# Trace_antenna_final_RFID_v10.net
KiCad netlist of a schematic drawn in EAGLE
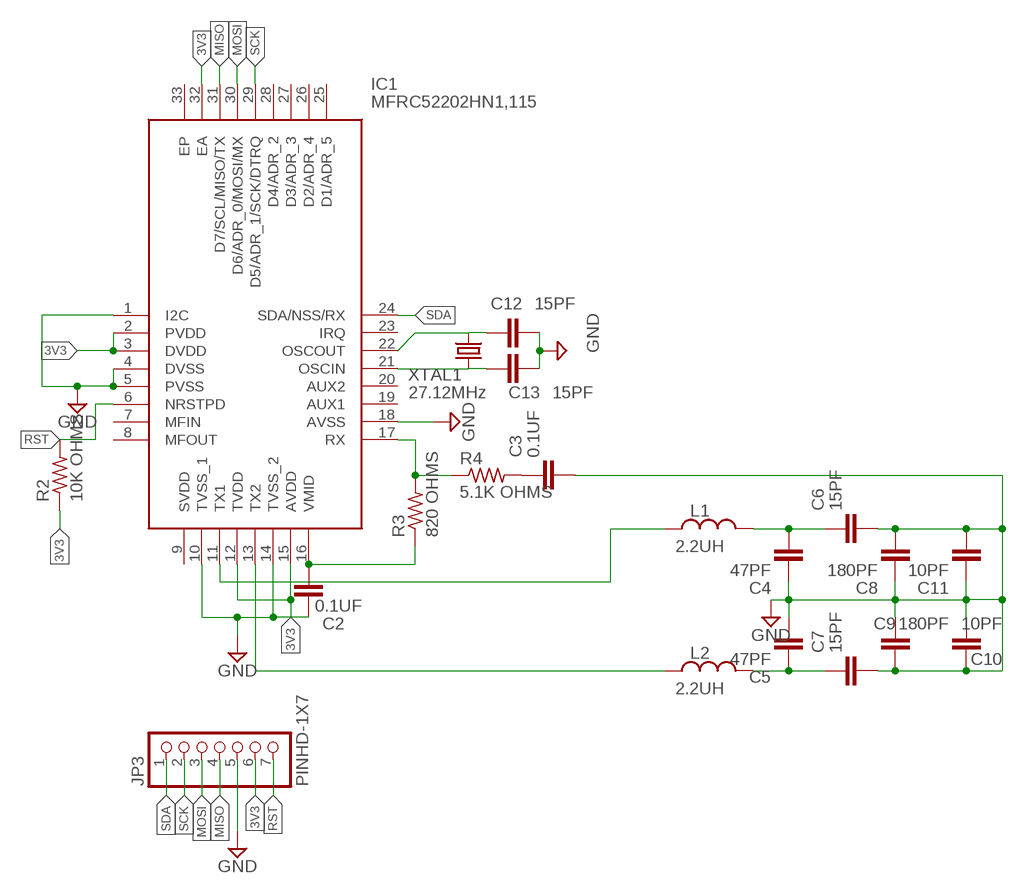
[diagram p0: schematic, sheet 1]

(export (version "E")
  (design (tool "Eeschema 10.0.6"))
  (components
    (comp (ref "C2")
      (value "0.1UF")
      (footprint "eagle-import:CAPC2012X110")
      (libsource (lib "eagle-import") (part "CCHIP-0805(2012-METRIC)_"))
    )
    (comp (ref "C3")
      (value "0.1UF")
      (footprint "eagle-import:CAPC2012X110")
      (libsource (lib "eagle-import") (part "CCHIP-0805(2012-METRIC)_"))
    )
    (comp (ref "C4")
      (value "47PF")
      (footprint "eagle-import:CAPC2012X110")
      (libsource (lib "eagle-import") (part "CCHIP-0805(2012-METRIC)_"))
    )
    (comp (ref "C5")
      (value "47PF")
      (footprint "eagle-import:CAPC2012X110")
      (libsource (lib "eagle-import") (part "CCHIP-0805(2012-METRIC)_"))
    )
    (comp (ref "C6")
      (value "15PF")
      (footprint "eagle-import:CAPC2012X110")
      (libsource (lib "eagle-import") (part "CCHIP-0805(2012-METRIC)_"))
    )
    (comp (ref "C7")
      (value "15PF")
      (footprint "eagle-import:CAPC2012X110")
      (libsource (lib "eagle-import") (part "CCHIP-0805(2012-METRIC)_"))
    )
    (comp (ref "C8")
      (value "180PF")
      (footprint "eagle-import:CAPC2012X110")
      (libsource (lib "eagle-import") (part "CCHIP-0805(2012-METRIC)_"))
    )
    (comp (ref "C9")
      (value "180PF")
      (footprint "eagle-import:CAPC2012X110")
      (libsource (lib "eagle-import") (part "CCHIP-0805(2012-METRIC)_"))
    )
    (comp (ref "C10")
      (value "10PF")
      (footprint "eagle-import:CAPC2012X110")
      (libsource (lib "eagle-import") (part "CCHIP-0805(2012-METRIC)_"))
    )
    (comp (ref "C11")
      (value "10PF")
      (footprint "eagle-import:CAPC2012X110")
      (libsource (lib "eagle-import") (part "CCHIP-0805(2012-METRIC)_"))
    )
    (comp (ref "C12")
      (value "15PF")
      (footprint "eagle-import:CAPC2012X110")
      (libsource (lib "eagle-import") (part "CCHIP-0805(2012-METRIC)_"))
    )
    (comp (ref "C13")
      (value "15PF")
      (footprint "eagle-import:CAPC2012X110")
      (libsource (lib "eagle-import") (part "CCHIP-0805(2012-METRIC)_"))
    )
    (comp (ref "IC1")
      (value "MFRC52202HN1,115")
      (footprint "eagle-import:QFN50P500X500X100-33N")
      (fields (field (name "MOUSER_PART_NUMBER") "771-MFRC52202HN1115"))
      (libsource (lib "eagle-import") (part "MFRC52202HN1,115"))
    )
    (comp (ref "JP3")
      (value "PINHD-1X7")
      (footprint "eagle-import:1X07")
      (libsource (lib "eagle-import") (part "PINHD-1X7"))
    )
    (comp (ref "L1")
      (value "2.2UH")
      (footprint "eagle-import:INDC2009X120")
      (libsource (lib "eagle-import") (part "LCHIP-0805(2012-METRIC)_"))
    )
    (comp (ref "L2")
      (value "2.2UH")
      (footprint "eagle-import:INDC2009X120")
      (libsource (lib "eagle-import") (part "LCHIP-0805(2012-METRIC)_"))
    )
    (comp (ref "R2")
      (value "10K OHMS")
      (footprint "eagle-import:RESC2012X65")
      (libsource (lib "eagle-import") (part "R-USCHIP-0805(2012-METRIC)_"))
    )
    (comp (ref "R3")
      (value "820 OHMS")
      (footprint "eagle-import:RESC2012X65")
      (libsource (lib "eagle-import") (part "R-USCHIP-0805(2012-METRIC)_"))
    )
    (comp (ref "R4")
      (value "5.1K OHMS")
      (footprint "eagle-import:RESC2012X65")
      (libsource (lib "eagle-import") (part "R-USCHIP-0805(2012-METRIC)_"))
    )
    (comp (ref "XTAL1")
      (value "27.12MHz")
      (footprint "eagle-import:XTALRR488W45L1150T500H350B")
      (libsource (lib "eagle-import") (part "CRYSTALHC49-11.5L_"))
    )
  )
  (nets
    (net (code "1") (name "3V3") (class "Default")
      (node (ref "IC1") (pin "12") (pinfunction "TVDD_12") (pintype "bidirectional"))
      (node (ref "IC1") (pin "15") (pinfunction "AVDD_15") (pintype "bidirectional"))
      (node (ref "IC1") (pin "2") (pinfunction "PVDD_2") (pintype "bidirectional"))
      (node (ref "IC1") (pin "3") (pinfunction "DVDD_3") (pintype "bidirectional"))
      (node (ref "IC1") (pin "32") (pinfunction "EA_32") (pintype "bidirectional"))
      (node (ref "JP3") (pin "6") (pinfunction "6_6") (pintype "passive"))
      (node (ref "R2") (pin "1") (pinfunction "1_1") (pintype "passive"))
    )
    (net (code "2") (name "GND") (class "Default")
      (node (ref "C10") (pin "1") (pinfunction "1_1") (pintype "passive"))
      (node (ref "C10") (pin "2") (pinfunction "2_2") (pintype "passive"))
      (node (ref "C11") (pin "1") (pinfunction "1_1") (pintype "passive"))
      (node (ref "C11") (pin "2") (pinfunction "2_2") (pintype "passive"))
      (node (ref "C12") (pin "2") (pinfunction "2_2") (pintype "passive"))
      (node (ref "C13") (pin "2") (pinfunction "2_2") (pintype "passive"))
      (node (ref "C2") (pin "1") (pinfunction "1_1") (pintype "passive"))
      (node (ref "C3") (pin "2") (pinfunction "2_2") (pintype "passive"))
      (node (ref "C4") (pin "1") (pinfunction "1_1") (pintype "passive"))
      (node (ref "C5") (pin "2") (pinfunction "2_2") (pintype "passive"))
      (node (ref "C6") (pin "2") (pinfunction "2_2") (pintype "passive"))
      (node (ref "C7") (pin "2") (pinfunction "2_2") (pintype "passive"))
      (node (ref "C8") (pin "1") (pinfunction "1_1") (pintype "passive"))
      (node (ref "C8") (pin "2") (pinfunction "2_2") (pintype "passive"))
      (node (ref "C9") (pin "1") (pinfunction "1_1") (pintype "passive"))
      (node (ref "C9") (pin "2") (pinfunction "2_2") (pintype "passive"))
      (node (ref "IC1") (pin "1") (pinfunction "I2C_1") (pintype "bidirectional"))
      (node (ref "IC1") (pin "10") (pinfunction "TVSS_1_10") (pintype "bidirectional"))
      (node (ref "IC1") (pin "14") (pinfunction "TVSS_2_14") (pintype "bidirectional"))
      (node (ref "IC1") (pin "18") (pinfunction "AVSS_18") (pintype "bidirectional"))
      (node (ref "IC1") (pin "4") (pinfunction "DVSS_4") (pintype "bidirectional"))
      (node (ref "IC1") (pin "5") (pinfunction "PVSS_5") (pintype "bidirectional"))
      (node (ref "JP3") (pin "5") (pinfunction "5_5") (pintype "passive"))
    )
    (net (code "3") (name "MISO") (class "Default")
      (node (ref "IC1") (pin "31") (pinfunction "D7/SCL/MISO/TX_31") (pintype "bidirectional"))
      (node (ref "JP3") (pin "4") (pinfunction "4_4") (pintype "passive"))
    )
    (net (code "4") (name "MOSI") (class "Default")
      (node (ref "IC1") (pin "30") (pinfunction "D6/ADR_0/MOSI/MX_30") (pintype "bidirectional"))
      (node (ref "JP3") (pin "3") (pinfunction "3_3") (pintype "passive"))
    )
    (net (code "5") (name "Net-(C3-Pad1)") (class "Default")
      (node (ref "C3") (pin "1") (pinfunction "1_1") (pintype "passive"))
      (node (ref "R4") (pin "2") (pinfunction "2_2") (pintype "passive"))
    )
    (net (code "6") (name "Net-(C4-Pad2)") (class "Default")
      (node (ref "C4") (pin "2") (pinfunction "2_2") (pintype "passive"))
      (node (ref "C6") (pin "1") (pinfunction "1_1") (pintype "passive"))
      (node (ref "L1") (pin "2") (pinfunction "2_2") (pintype "passive"))
    )
    (net (code "7") (name "Net-(C5-Pad1)") (class "Default")
      (node (ref "C5") (pin "1") (pinfunction "1_1") (pintype "passive"))
      (node (ref "C7") (pin "1") (pinfunction "1_1") (pintype "passive"))
      (node (ref "L2") (pin "2") (pinfunction "2_2") (pintype "passive"))
    )
    (net (code "8") (name "Net-(IC1-OSCIN)") (class "Default")
      (node (ref "C13") (pin "1") (pinfunction "1_1") (pintype "passive"))
      (node (ref "IC1") (pin "21") (pinfunction "OSCIN_21") (pintype "bidirectional"))
      (node (ref "XTAL1") (pin "1") (pinfunction "1_1") (pintype "passive"))
    )
    (net (code "9") (name "Net-(IC1-OSCOUT)") (class "Default")
      (node (ref "C12") (pin "1") (pinfunction "1_1") (pintype "passive"))
      (node (ref "IC1") (pin "22") (pinfunction "OSCOUT_22") (pintype "bidirectional"))
      (node (ref "XTAL1") (pin "2") (pinfunction "2_2") (pintype "passive"))
    )
    (net (code "10") (name "Net-(IC1-RX)") (class "Default")
      (node (ref "IC1") (pin "17") (pinfunction "RX_17") (pintype "bidirectional"))
      (node (ref "R3") (pin "2") (pinfunction "2_2") (pintype "passive"))
      (node (ref "R4") (pin "1") (pinfunction "1_1") (pintype "passive"))
    )
    (net (code "11") (name "Net-(IC1-TX1)") (class "Default")
      (node (ref "IC1") (pin "11") (pinfunction "TX1_11") (pintype "bidirectional"))
      (node (ref "L1") (pin "1") (pinfunction "1_1") (pintype "passive"))
    )
    (net (code "12") (name "Net-(IC1-TX2)") (class "Default")
      (node (ref "IC1") (pin "13") (pinfunction "TX2_13") (pintype "bidirectional"))
      (node (ref "L2") (pin "1") (pinfunction "1_1") (pintype "passive"))
    )
    (net (code "13") (name "Net-(IC1-VMID)") (class "Default")
      (node (ref "C2") (pin "2") (pinfunction "2_2") (pintype "passive"))
      (node (ref "IC1") (pin "16") (pinfunction "VMID_16") (pintype "bidirectional"))
      (node (ref "R3") (pin "1") (pinfunction "1_1") (pintype "passive"))
    )
    (net (code "14") (name "RST") (class "Default")
      (node (ref "IC1") (pin "6") (pinfunction "NRSTPD_6") (pintype "bidirectional"))
      (node (ref "JP3") (pin "7") (pinfunction "7_7") (pintype "passive"))
      (node (ref "R2") (pin "2") (pinfunction "2_2") (pintype "passive"))
    )
    (net (code "15") (name "SCK") (class "Default")
      (node (ref "IC1") (pin "29") (pinfunction "D5/ADR_1/SCK/DTRQ_29") (pintype "bidirectional"))
      (node (ref "JP3") (pin "2") (pinfunction "2_2") (pintype "passive"))
    )
    (net (code "16") (name "SDA") (class "Default")
      (node (ref "IC1") (pin "24") (pinfunction "SDA/NSS/RX_24") (pintype "bidirectional"))
      (node (ref "JP3") (pin "1") (pinfunction "1_1") (pintype "passive"))
    )
    (net (code "17") (name "unconnected-(IC1-AUX1-Pad19)") (class "Default")
      (node (ref "IC1") (pin "19") (pinfunction "AUX1_19") (pintype "bidirectional"))
    )
    (net (code "18") (name "unconnected-(IC1-AUX2-Pad20)") (class "Default")
      (node (ref "IC1") (pin "20") (pinfunction "AUX2_20") (pintype "bidirectional"))
    )
    (net (code "19") (name "unconnected-(IC1-D1{slash}ADR_5-Pad25)") (class "Default")
      (node (ref "IC1") (pin "25") (pinfunction "D1/ADR_5_25") (pintype "bidirectional"))
    )
    (net (code "20") (name "unconnected-(IC1-D2{slash}ADR_4-Pad26)") (class "Default")
      (node (ref "IC1") (pin "26") (pinfunction "D2/ADR_4_26") (pintype "bidirectional"))
    )
    (net (code "21") (name "unconnected-(IC1-D3{slash}ADR_3-Pad27)") (class "Default")
      (node (ref "IC1") (pin "27") (pinfunction "D3/ADR_3_27") (pintype "bidirectional"))
    )
    (net (code "22") (name "unconnected-(IC1-D4{slash}ADR_2-Pad28)") (class "Default")
      (node (ref "IC1") (pin "28") (pinfunction "D4/ADR_2_28") (pintype "bidirectional"))
    )
    (net (code "23") (name "unconnected-(IC1-EP-Pad33)") (class "Default")
      (node (ref "IC1") (pin "33") (pinfunction "EP_33") (pintype "bidirectional"))
    )
    (net (code "24") (name "unconnected-(IC1-IRQ-Pad23)") (class "Default")
      (node (ref "IC1") (pin "23") (pinfunction "IRQ_23") (pintype "bidirectional"))
    )
    (net (code "25") (name "unconnected-(IC1-MFIN-Pad7)") (class "Default")
      (node (ref "IC1") (pin "7") (pinfunction "MFIN_7") (pintype "bidirectional"))
    )
    (net (code "26") (name "unconnected-(IC1-MFOUT-Pad8)") (class "Default")
      (node (ref "IC1") (pin "8") (pinfunction "MFOUT_8") (pintype "bidirectional"))
    )
    (net (code "27") (name "unconnected-(IC1-SVDD-Pad9)") (class "Default")
      (node (ref "IC1") (pin "9") (pinfunction "SVDD_9") (pintype "bidirectional"))
    )
  )
)
